# Mgmt.net
KiCad netlist of a schematic drawn in Altium Designer
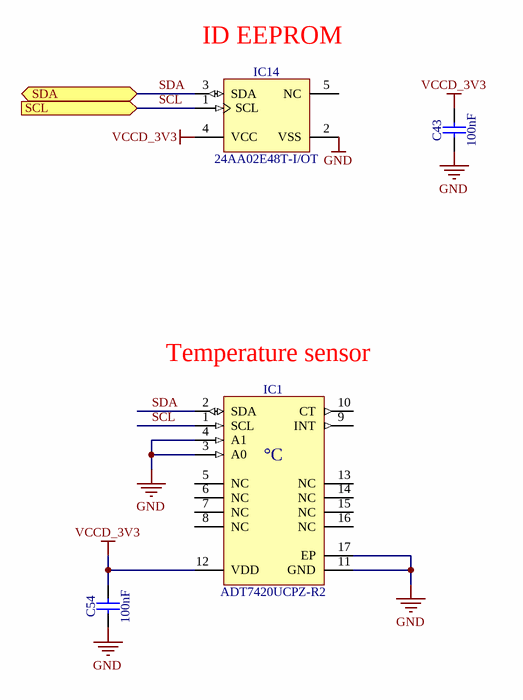
[diagram p0: Mgmt.SchDoc]

(export (version "E")
  (design (tool "Eeschema 10.0.6"))
  (components
    (comp (ref "C43")
      (value "100nF")
      (footprint "CAPC1005X55N")
      (description "Non-polarised capacitor")
      (fields
        (field (name "PART NUMBER") "CC0402_100NF_16V_10%_X5R")
        (field (name "VOLTAGE") "16V")
        (field (name "AUTHOR") "CERN DEM JLC")
      )
      (libsource (lib "Capacitors") (part "Capacitor - non polarized"))
    )
    (comp (ref "C54")
      (value "100nF")
      (footprint "CAPC1005X55N")
      (description "Non-polarised capacitor")
      (fields
        (field (name "PART NUMBER") "CC0402_100NF_16V_10%_X5R")
        (field (name "VOLTAGE") "16V")
        (field (name "AUTHOR") "CERN DEM JLC")
      )
      (libsource (lib "Capacitors") (part "Capacitor - non polarized"))
    )
    (comp (ref "IC1")
      (value "ADT7420UCPZ-R2")
      (footprint "QFN65P400X400X80-17N-S270")
      (description "±0.25°C Accurate, 16-Bit Digital I2C Temperature Sensor")
      (fields (field (name "MANUFACTURER") "ANALOG DEVICES") (field (name "AUTHOR") "CERN DEM JLC"))
      (libsource (lib "ICs And Semiconductors") (part "ADT7420"))
    )
    (comp (ref "IC14")
      (value "24AA02E48T-I/OT")
      (footprint "SOT95P280X145-5N")
      (description "1.7V-5.5V, 2K I2C Serial EEPROM With EUI-48 Node Identity")
      (fields (field (name "MANUFACTURER") "MICROCHIP TECHNOLOGY") (field (name "AUTHOR") "CERN DEM MR"))
      (libsource (lib "ICs And Semiconductors") (part "24AA02E48T-I/OT"))
    )
  )
  (nets
    (net (code "1") (name "/SCL") (class "Default")
      (node (ref "IC1") (pin "1") (pinfunction "SCL_1") (pintype "input"))
      (node (ref "IC14") (pin "1") (pinfunction "SCL_1") (pintype "input"))
    )
    (net (code "2") (name "/SDA") (class "Default")
      (node (ref "IC1") (pin "2") (pinfunction "SDA_2") (pintype "bidirectional"))
      (node (ref "IC14") (pin "3") (pinfunction "SDA_3") (pintype "bidirectional"))
    )
    (net (code "3") (name "GND") (class "Default")
      (node (ref "C43") (pin "1") (pinfunction "1_1") (pintype "passive"))
      (node (ref "C54") (pin "1") (pinfunction "1_1") (pintype "passive"))
      (node (ref "IC1") (pin "11") (pinfunction "GND_11") (pintype "power_in"))
      (node (ref "IC1") (pin "17") (pinfunction "EP_17") (pintype "power_in"))
      (node (ref "IC1") (pin "3") (pinfunction "A0_3") (pintype "input"))
      (node (ref "IC1") (pin "4") (pinfunction "A1_4") (pintype "input"))
      (node (ref "IC14") (pin "2") (pinfunction "VSS_2") (pintype "power_in"))
    )
    (net (code "4") (name "VCCD_3V3") (class "Default")
      (node (ref "C43") (pin "2") (pinfunction "2_2") (pintype "passive"))
      (node (ref "C54") (pin "2") (pinfunction "2_2") (pintype "passive"))
      (node (ref "IC1") (pin "12") (pinfunction "VDD_12") (pintype "power_in"))
      (node (ref "IC14") (pin "4") (pinfunction "VCC_4") (pintype "power_in"))
    )
    (net (code "5") (name "unconnected-(IC1-CT-Pad10)") (class "Default")
      (node (ref "IC1") (pin "10") (pinfunction "CT_10") (pintype "output"))
    )
    (net (code "6") (name "unconnected-(IC1-INT-Pad9)") (class "Default")
      (node (ref "IC1") (pin "9") (pinfunction "INT_9") (pintype "output"))
    )
    (net (code "7") (name "unconnected-(IC1-NC-Pad5)") (class "Default")
      (node (ref "IC1") (pin "5") (pinfunction "NC_5") (pintype "passive"))
    )
    (net (code "8") (name "unconnected-(IC1-NC-Pad6)") (class "Default")
      (node (ref "IC1") (pin "6") (pinfunction "NC_6") (pintype "passive"))
    )
    (net (code "9") (name "unconnected-(IC1-NC-Pad7)") (class "Default")
      (node (ref "IC1") (pin "7") (pinfunction "NC_7") (pintype "passive"))
    )
    (net (code "10") (name "unconnected-(IC1-NC-Pad8)") (class "Default")
      (node (ref "IC1") (pin "8") (pinfunction "NC_8") (pintype "passive"))
    )
    (net (code "11") (name "unconnected-(IC1-NC-Pad13)") (class "Default")
      (node (ref "IC1") (pin "13") (pinfunction "NC_13") (pintype "passive"))
    )
    (net (code "12") (name "unconnected-(IC1-NC-Pad14)") (class "Default")
      (node (ref "IC1") (pin "14") (pinfunction "NC_14") (pintype "passive"))
    )
    (net (code "13") (name "unconnected-(IC1-NC-Pad15)") (class "Default")
      (node (ref "IC1") (pin "15") (pinfunction "NC_15") (pintype "passive"))
    )
    (net (code "14") (name "unconnected-(IC1-NC-Pad16)") (class "Default")
      (node (ref "IC1") (pin "16") (pinfunction "NC_16") (pintype "passive"))
    )
    (net (code "15") (name "unconnected-(IC14-NC-Pad5)") (class "Default")
      (node (ref "IC14") (pin "5") (pinfunction "NC_5") (pintype "passive"))
    )
  )
)
